# Buffered_mult_rev_3.net
KiCad netlist of a schematic drawn in EAGLE
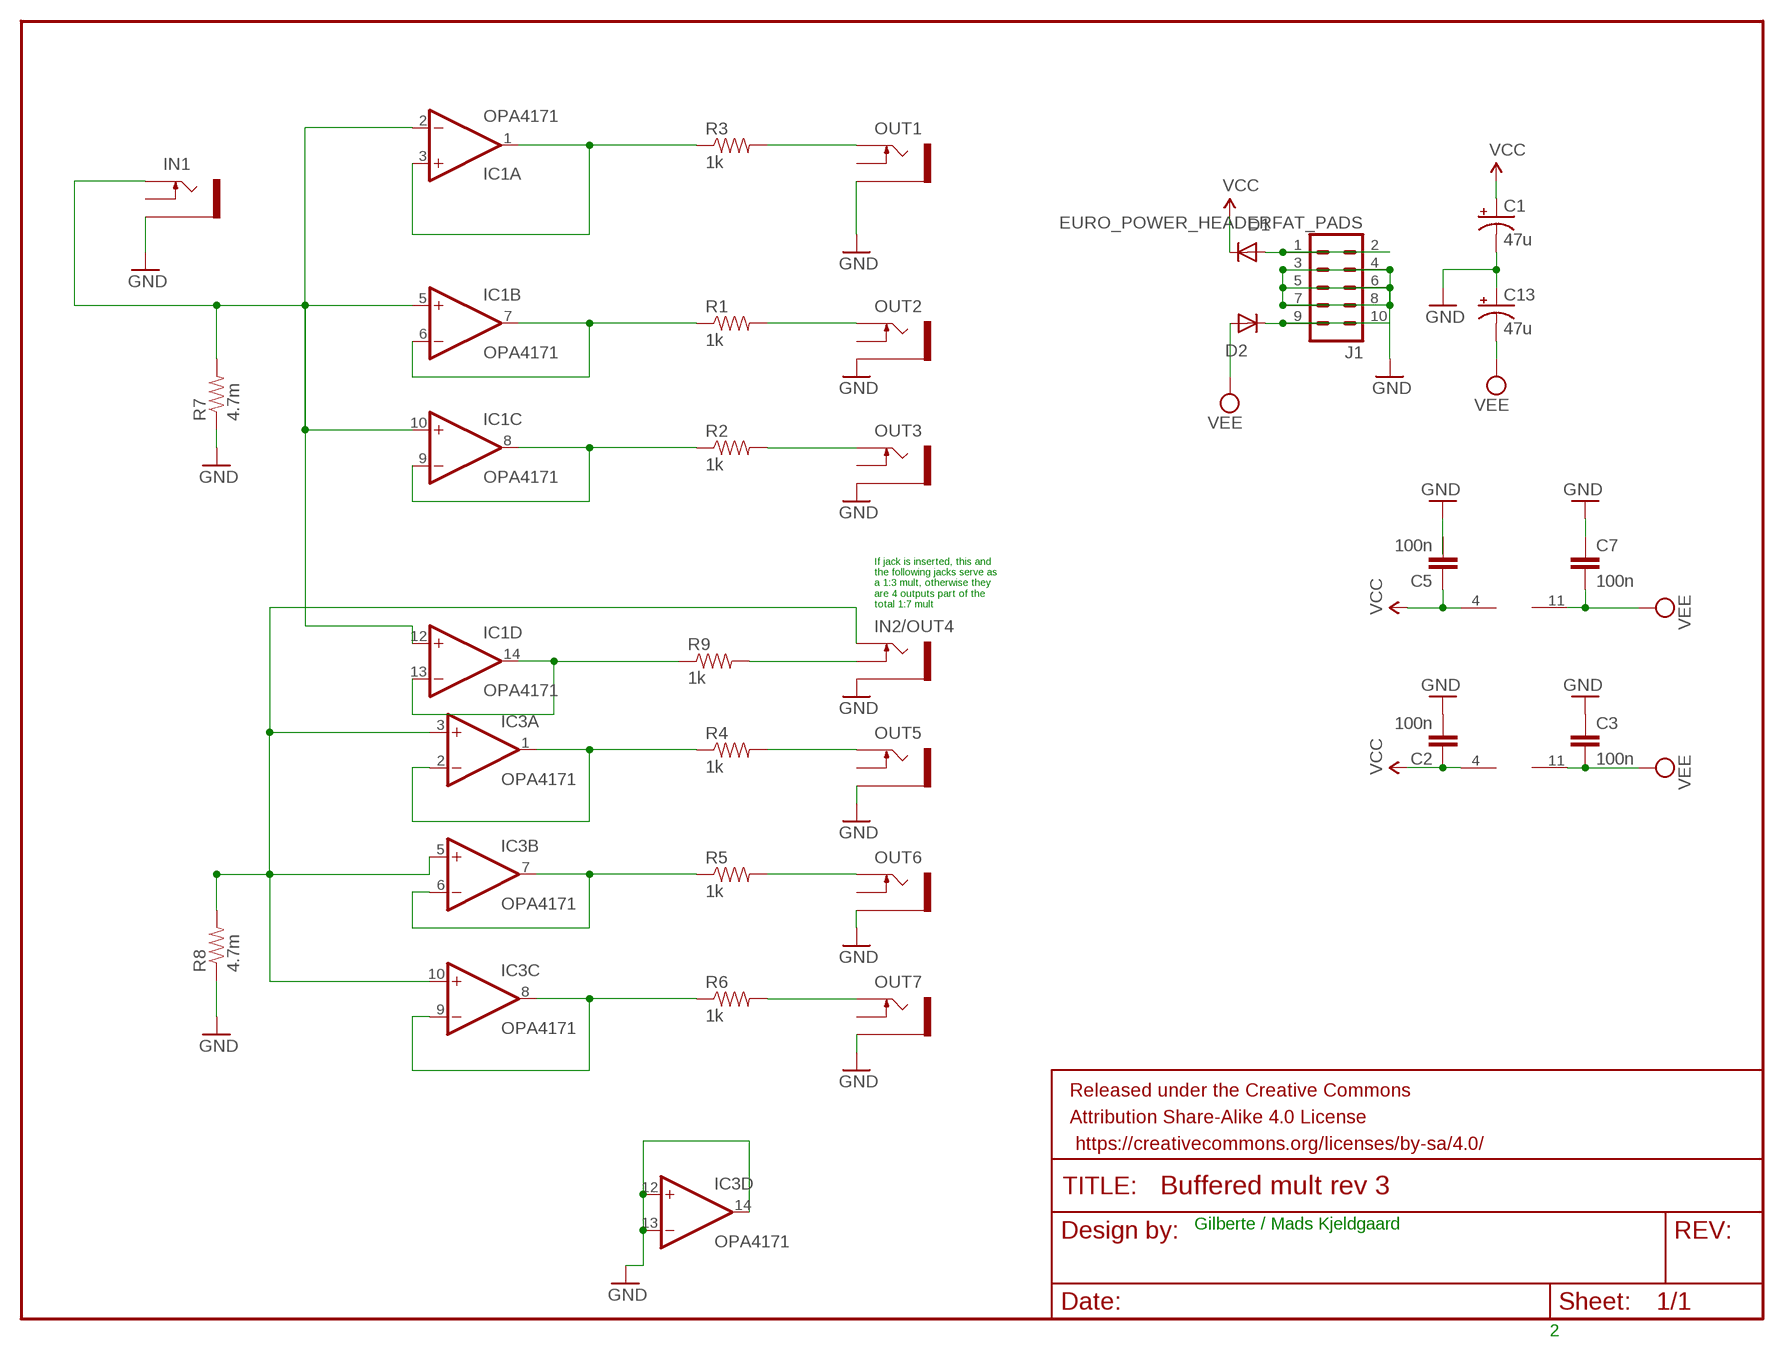
[diagram p0: schematic, sheet 1]

(export (version "E")
  (design (tool "Eeschema 10.0.6"))
  (components
    (comp (ref "C1")
      (value "47u")
      (footprint "eagle-import:PANASONIC_D")
      (libsource (lib "eagle-import") (part "CPOL-USD"))
    )
    (comp (ref "C2")
      (value "100n")
      (footprint "eagle-import:1206")
      (libsource (lib "eagle-import") (part "CAP1206"))
    )
    (comp (ref "C3")
      (value "100n")
      (footprint "eagle-import:1206")
      (libsource (lib "eagle-import") (part "CAP1206"))
    )
    (comp (ref "C5")
      (value "100n")
      (footprint "eagle-import:1206")
      (libsource (lib "eagle-import") (part "CAP1206"))
    )
    (comp (ref "C7")
      (value "100n")
      (footprint "eagle-import:1206")
      (libsource (lib "eagle-import") (part "CAP1206"))
    )
    (comp (ref "C13")
      (value "47u")
      (footprint "eagle-import:PANASONIC_D")
      (libsource (lib "eagle-import") (part "CPOL-USD"))
    )
    (comp (ref "D1")
      (value "1N5819HW")
      (footprint "eagle-import:SOD123")
      (libsource (lib "eagle-import") (part "DIODE-SOD123"))
    )
    (comp (ref "D2")
      (value "1N5819HW")
      (footprint "eagle-import:SOD123")
      (libsource (lib "eagle-import") (part "DIODE-SOD123"))
    )
    (comp (ref "FRAME1")
      (value "FRAME-LETTER")
      (footprint "eagle-import:CREATIVE_COMMONS")
      (libsource (lib "eagle-import") (part "FRAME-LETTER"))
    )
    (comp (ref "IC1")
      (value "OPA4171")
      (footprint "eagle-import:TSSOP14")
      (libsource (lib "eagle-import") (part "TL074PW"))
    )
    (comp (ref "IC3")
      (value "OPA4171")
      (footprint "eagle-import:TSSOP14")
      (libsource (lib "eagle-import") (part "TL074PW"))
    )
    (comp (ref "IN1")
      (value "PJ302M")
      (footprint "eagle-import:PJ302M")
      (libsource (lib "eagle-import") (part "PJ302M"))
    )
    (comp (ref "IN2/OUT4")
      (value "PJ302M")
      (footprint "eagle-import:PJ302M")
      (libsource (lib "eagle-import") (part "PJ302M"))
    )
    (comp (ref "J1")
      (value "EURO_POWER_HEADERFAT_PADS")
      (footprint "eagle-import:EURO_PWR_HEADER_FAT")
      (libsource (lib "eagle-import") (part "EURO_POWER_HEADERFAT_PADS"))
    )
    (comp (ref "OUT1")
      (value "PJ302M")
      (footprint "eagle-import:PJ302M")
      (libsource (lib "eagle-import") (part "PJ302M"))
    )
    (comp (ref "OUT2")
      (value "PJ302M")
      (footprint "eagle-import:PJ302M")
      (libsource (lib "eagle-import") (part "PJ302M"))
    )
    (comp (ref "OUT3")
      (value "PJ302M")
      (footprint "eagle-import:PJ302M")
      (libsource (lib "eagle-import") (part "PJ302M"))
    )
    (comp (ref "OUT5")
      (value "PJ302M")
      (footprint "eagle-import:PJ302M")
      (libsource (lib "eagle-import") (part "PJ302M"))
    )
    (comp (ref "OUT6")
      (value "PJ302M")
      (footprint "eagle-import:PJ302M")
      (libsource (lib "eagle-import") (part "PJ302M"))
    )
    (comp (ref "OUT7")
      (value "PJ302M")
      (footprint "eagle-import:PJ302M")
      (libsource (lib "eagle-import") (part "PJ302M"))
    )
    (comp (ref "R1")
      (value "1k")
      (footprint "eagle-import:1206")
      (libsource (lib "eagle-import") (part "RESISTOR1206"))
    )
    (comp (ref "R2")
      (value "1k")
      (footprint "eagle-import:1206")
      (libsource (lib "eagle-import") (part "RESISTOR1206"))
    )
    (comp (ref "R3")
      (value "1k")
      (footprint "eagle-import:1206")
      (libsource (lib "eagle-import") (part "RESISTOR1206"))
    )
    (comp (ref "R4")
      (value "1k")
      (footprint "eagle-import:1206")
      (libsource (lib "eagle-import") (part "RESISTOR1206"))
    )
    (comp (ref "R5")
      (value "1k")
      (footprint "eagle-import:1206")
      (libsource (lib "eagle-import") (part "RESISTOR1206"))
    )
    (comp (ref "R6")
      (value "1k")
      (footprint "eagle-import:1206")
      (libsource (lib "eagle-import") (part "RESISTOR1206"))
    )
    (comp (ref "R7")
      (value "4.7m")
      (footprint "eagle-import:1206")
      (libsource (lib "eagle-import") (part "RESISTOR1206"))
    )
    (comp (ref "R8")
      (value "4.7m")
      (footprint "eagle-import:1206")
      (libsource (lib "eagle-import") (part "RESISTOR1206"))
    )
    (comp (ref "R9")
      (value "1k")
      (footprint "eagle-import:1206")
      (libsource (lib "eagle-import") (part "RESISTOR1206"))
    )
  )
  (nets
    (net (code "1") (name "GND") (class "Default")
      (node (ref "C1") (pin "-") (pinfunction "-_-") (pintype "passive"))
      (node (ref "C13") (pin "+") (pinfunction "+_+") (pintype "passive"))
      (node (ref "C2") (pin "2") (pinfunction "2_2") (pintype "passive"))
      (node (ref "C3") (pin "1") (pinfunction "1_1") (pintype "passive"))
      (node (ref "C5") (pin "2") (pinfunction "2_2") (pintype "passive"))
      (node (ref "C7") (pin "1") (pinfunction "1_1") (pintype "passive"))
      (node (ref "IC3") (pin "12") (pinfunction "+IN_12") (pintype "input"))
      (node (ref "IC3") (pin "13") (pinfunction "-IN_13") (pintype "input"))
      (node (ref "IC3") (pin "14") (pinfunction "OUT_14") (pintype "output"))
      (node (ref "IN1") (pin "GND") (pinfunction "SLEEVE_GND") (pintype "passive"))
      (node (ref "IN2/OUT4") (pin "GND") (pinfunction "SLEEVE_GND") (pintype "passive"))
      (node (ref "J1") (pin "3") (pinfunction "3_3") (pintype "passive"))
      (node (ref "J1") (pin "4") (pinfunction "4_4") (pintype "passive"))
      (node (ref "J1") (pin "5") (pinfunction "5_5") (pintype "passive"))
      (node (ref "J1") (pin "6") (pinfunction "6_6") (pintype "passive"))
      (node (ref "J1") (pin "7") (pinfunction "7_7") (pintype "passive"))
      (node (ref "J1") (pin "8") (pinfunction "8_8") (pintype "passive"))
      (node (ref "OUT1") (pin "GND") (pinfunction "SLEEVE_GND") (pintype "passive"))
      (node (ref "OUT2") (pin "GND") (pinfunction "SLEEVE_GND") (pintype "passive"))
      (node (ref "OUT3") (pin "GND") (pinfunction "SLEEVE_GND") (pintype "passive"))
      (node (ref "OUT5") (pin "GND") (pinfunction "SLEEVE_GND") (pintype "passive"))
      (node (ref "OUT6") (pin "GND") (pinfunction "SLEEVE_GND") (pintype "passive"))
      (node (ref "OUT7") (pin "GND") (pinfunction "SLEEVE_GND") (pintype "passive"))
      (node (ref "R7") (pin "1") (pinfunction "1_1") (pintype "passive"))
      (node (ref "R8") (pin "1") (pinfunction "1_1") (pintype "passive"))
    )
    (net (code "2") (name "Net-(D1-PadA)") (class "Default")
      (node (ref "D1") (pin "A") (pinfunction "A_A") (pintype "passive"))
      (node (ref "J1") (pin "1") (pinfunction "1_1") (pintype "passive"))
      (node (ref "J1") (pin "2") (pinfunction "2_2") (pintype "passive"))
    )
    (net (code "3") (name "Net-(D2-PadC)") (class "Default")
      (node (ref "D2") (pin "C") (pinfunction "C_C") (pintype "passive"))
      (node (ref "J1") (pin "10") (pinfunction "10_10") (pintype "passive"))
      (node (ref "J1") (pin "9") (pinfunction "9_9") (pintype "passive"))
    )
    (net (code "4") (name "Net-(IC1A-+IN)") (class "Default")
      (node (ref "IC1") (pin "1") (pinfunction "OUT_1") (pintype "output"))
      (node (ref "IC1") (pin "3") (pinfunction "+IN_3") (pintype "input"))
      (node (ref "R3") (pin "1") (pinfunction "1_1") (pintype "passive"))
    )
    (net (code "5") (name "Net-(IC1A--IN)") (class "Default")
      (node (ref "IC1") (pin "10") (pinfunction "+IN_10") (pintype "input"))
      (node (ref "IC1") (pin "12") (pinfunction "+IN_12") (pintype "input"))
      (node (ref "IC1") (pin "2") (pinfunction "-IN_2") (pintype "input"))
      (node (ref "IC1") (pin "5") (pinfunction "+IN_5") (pintype "input"))
      (node (ref "IN1") (pin "TIP") (pinfunction "TIP_TIP") (pintype "passive"))
      (node (ref "R7") (pin "2") (pinfunction "2_2") (pintype "passive"))
    )
    (net (code "6") (name "Net-(IC1B--IN)") (class "Default")
      (node (ref "IC1") (pin "6") (pinfunction "-IN_6") (pintype "input"))
      (node (ref "IC1") (pin "7") (pinfunction "OUT_7") (pintype "output"))
      (node (ref "R1") (pin "1") (pinfunction "1_1") (pintype "passive"))
    )
    (net (code "7") (name "Net-(IC1C--IN)") (class "Default")
      (node (ref "IC1") (pin "8") (pinfunction "OUT_8") (pintype "output"))
      (node (ref "IC1") (pin "9") (pinfunction "-IN_9") (pintype "input"))
      (node (ref "R2") (pin "1") (pinfunction "1_1") (pintype "passive"))
    )
    (net (code "8") (name "Net-(IC1D--IN)") (class "Default")
      (node (ref "IC1") (pin "13") (pinfunction "-IN_13") (pintype "input"))
      (node (ref "IC1") (pin "14") (pinfunction "OUT_14") (pintype "output"))
      (node (ref "R9") (pin "1") (pinfunction "1_1") (pintype "passive"))
    )
    (net (code "9") (name "Net-(IC3A-+IN)") (class "Default")
      (node (ref "IC3") (pin "10") (pinfunction "+IN_10") (pintype "input"))
      (node (ref "IC3") (pin "3") (pinfunction "+IN_3") (pintype "input"))
      (node (ref "IC3") (pin "5") (pinfunction "+IN_5") (pintype "input"))
      (node (ref "IN2/OUT4") (pin "TIP") (pinfunction "TIP_TIP") (pintype "passive"))
      (node (ref "R8") (pin "2") (pinfunction "2_2") (pintype "passive"))
    )
    (net (code "10") (name "Net-(IC3A--IN)") (class "Default")
      (node (ref "IC3") (pin "1") (pinfunction "OUT_1") (pintype "output"))
      (node (ref "IC3") (pin "2") (pinfunction "-IN_2") (pintype "input"))
      (node (ref "R4") (pin "1") (pinfunction "1_1") (pintype "passive"))
    )
    (net (code "11") (name "Net-(IC3B--IN)") (class "Default")
      (node (ref "IC3") (pin "6") (pinfunction "-IN_6") (pintype "input"))
      (node (ref "IC3") (pin "7") (pinfunction "OUT_7") (pintype "output"))
      (node (ref "R5") (pin "1") (pinfunction "1_1") (pintype "passive"))
    )
    (net (code "12") (name "Net-(IC3C--IN)") (class "Default")
      (node (ref "IC3") (pin "8") (pinfunction "OUT_8") (pintype "output"))
      (node (ref "IC3") (pin "9") (pinfunction "-IN_9") (pintype "input"))
      (node (ref "R6") (pin "1") (pinfunction "1_1") (pintype "passive"))
    )
    (net (code "13") (name "Net-(IN2/OUT4-SWITCH)") (class "Default")
      (node (ref "IN2/OUT4") (pin "SW") (pinfunction "SWITCH_SW") (pintype "passive"))
      (node (ref "R9") (pin "2") (pinfunction "2_2") (pintype "passive"))
    )
    (net (code "14") (name "Net-(OUT1-PadTIP)") (class "Default")
      (node (ref "OUT1") (pin "TIP") (pinfunction "TIP_TIP") (pintype "passive"))
      (node (ref "R3") (pin "2") (pinfunction "2_2") (pintype "passive"))
    )
    (net (code "15") (name "Net-(OUT2-PadTIP)") (class "Default")
      (node (ref "OUT2") (pin "TIP") (pinfunction "TIP_TIP") (pintype "passive"))
      (node (ref "R1") (pin "2") (pinfunction "2_2") (pintype "passive"))
    )
    (net (code "16") (name "Net-(OUT3-PadTIP)") (class "Default")
      (node (ref "OUT3") (pin "TIP") (pinfunction "TIP_TIP") (pintype "passive"))
      (node (ref "R2") (pin "2") (pinfunction "2_2") (pintype "passive"))
    )
    (net (code "17") (name "Net-(OUT5-PadTIP)") (class "Default")
      (node (ref "OUT5") (pin "TIP") (pinfunction "TIP_TIP") (pintype "passive"))
      (node (ref "R4") (pin "2") (pinfunction "2_2") (pintype "passive"))
    )
    (net (code "18") (name "Net-(OUT6-PadTIP)") (class "Default")
      (node (ref "OUT6") (pin "TIP") (pinfunction "TIP_TIP") (pintype "passive"))
      (node (ref "R5") (pin "2") (pinfunction "2_2") (pintype "passive"))
    )
    (net (code "19") (name "Net-(OUT7-PadTIP)") (class "Default")
      (node (ref "OUT7") (pin "TIP") (pinfunction "TIP_TIP") (pintype "passive"))
      (node (ref "R6") (pin "2") (pinfunction "2_2") (pintype "passive"))
    )
    (net (code "20") (name "VCC") (class "Default")
      (node (ref "C1") (pin "+") (pinfunction "+_+") (pintype "passive"))
      (node (ref "C2") (pin "1") (pinfunction "1_1") (pintype "passive"))
      (node (ref "C5") (pin "1") (pinfunction "1_1") (pintype "passive"))
      (node (ref "D1") (pin "C") (pinfunction "C_C") (pintype "passive"))
      (node (ref "IC1") (pin "4") (pinfunction "V+_4") (pintype "power_in"))
      (node (ref "IC3") (pin "4") (pinfunction "V+_4") (pintype "power_in"))
    )
    (net (code "21") (name "VEE") (class "Default")
      (node (ref "C13") (pin "-") (pinfunction "-_-") (pintype "passive"))
      (node (ref "C3") (pin "2") (pinfunction "2_2") (pintype "passive"))
      (node (ref "C7") (pin "2") (pinfunction "2_2") (pintype "passive"))
      (node (ref "D2") (pin "A") (pinfunction "A_A") (pintype "passive"))
      (node (ref "IC1") (pin "11") (pinfunction "V-_11") (pintype "power_in"))
      (node (ref "IC3") (pin "11") (pinfunction "V-_11") (pintype "power_in"))
    )
    (net (code "22") (name "unconnected-(IN1-SWITCH-PadSW)") (class "Default")
      (node (ref "IN1") (pin "SW") (pinfunction "SWITCH_SW") (pintype "passive"))
    )
    (net (code "23") (name "unconnected-(OUT1-SWITCH-PadSW)") (class "Default")
      (node (ref "OUT1") (pin "SW") (pinfunction "SWITCH_SW") (pintype "passive"))
    )
    (net (code "24") (name "unconnected-(OUT2-SWITCH-PadSW)") (class "Default")
      (node (ref "OUT2") (pin "SW") (pinfunction "SWITCH_SW") (pintype "passive"))
    )
    (net (code "25") (name "unconnected-(OUT3-SWITCH-PadSW)") (class "Default")
      (node (ref "OUT3") (pin "SW") (pinfunction "SWITCH_SW") (pintype "passive"))
    )
    (net (code "26") (name "unconnected-(OUT5-SWITCH-PadSW)") (class "Default")
      (node (ref "OUT5") (pin "SW") (pinfunction "SWITCH_SW") (pintype "passive"))
    )
    (net (code "27") (name "unconnected-(OUT6-SWITCH-PadSW)") (class "Default")
      (node (ref "OUT6") (pin "SW") (pinfunction "SWITCH_SW") (pintype "passive"))
    )
    (net (code "28") (name "unconnected-(OUT7-SWITCH-PadSW)") (class "Default")
      (node (ref "OUT7") (pin "SW") (pinfunction "SWITCH_SW") (pintype "passive"))
    )
  )
)
